# STX165R_UAVCAN_module.net
KiCad netlist of a schematic drawn in Altium Designer
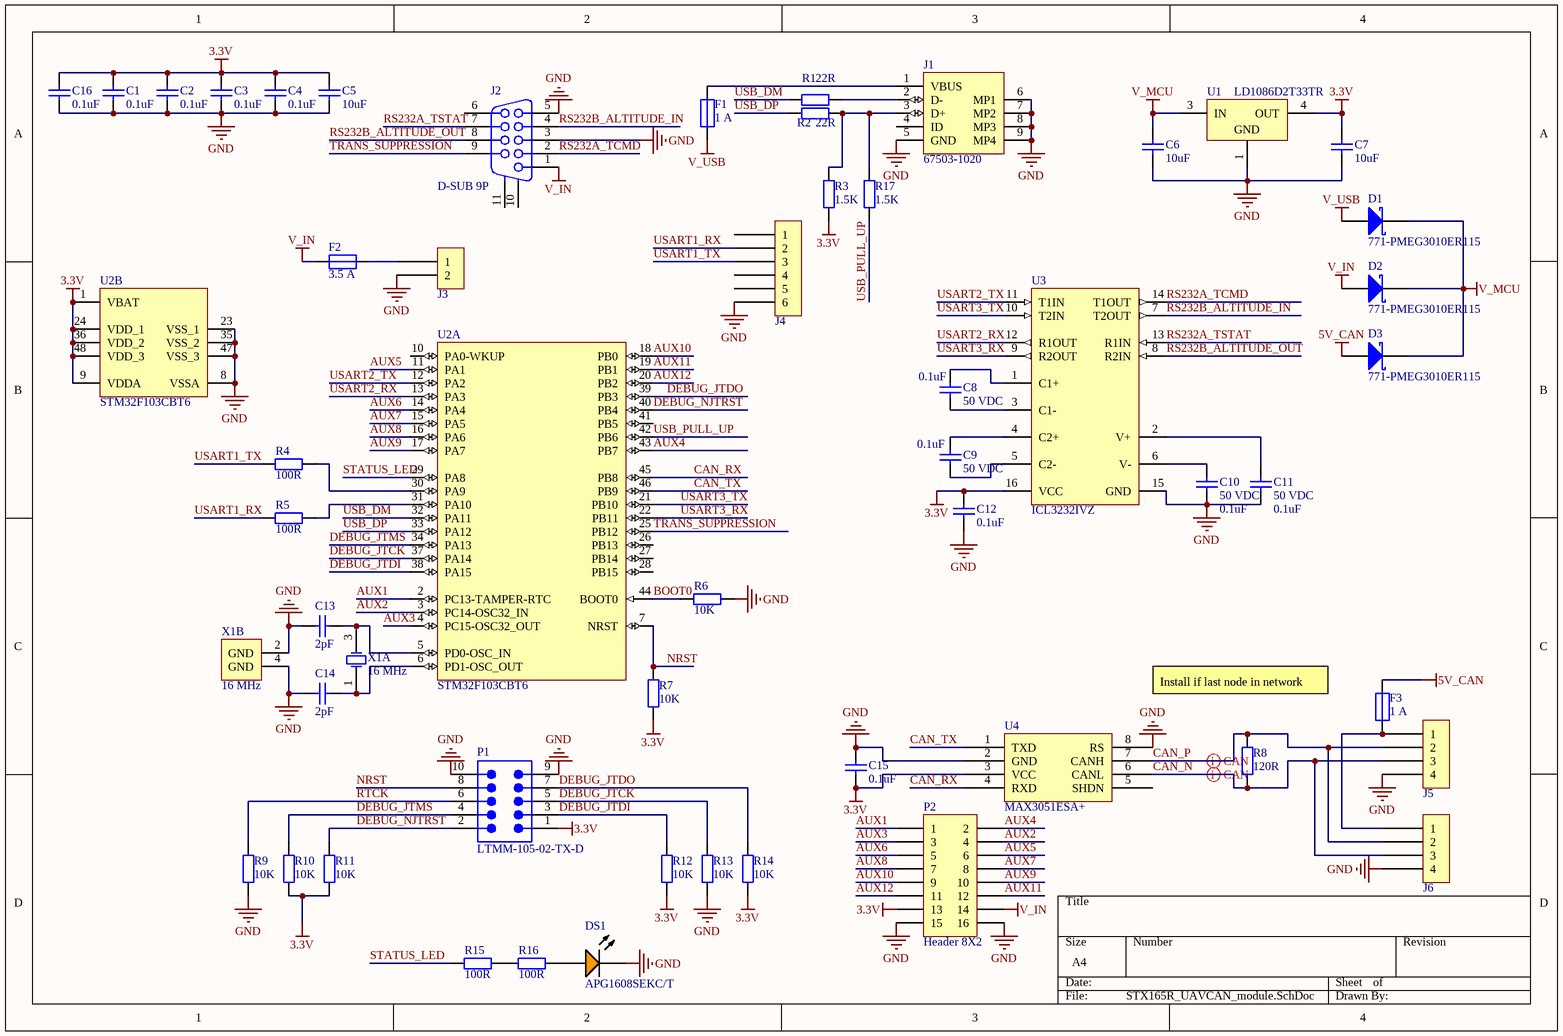
[diagram p0: STX165R_UAVCAN_module.SchDoc]

(export (version "E")
  (design (tool "Eeschema 10.0.6"))
  (components
    (comp (ref "C1")
      (value "0.1uF")
      (footprint "0603C_L")
      (description "CAP CER 0603 0.1uF 16V X7R 5%")
      (fields
        (field (name "MANUFACTURER") "Vishay / Vitramon")
        (field (name "MANUFACTURER PART NUMBER") "VJ0603Y104JXJPW1BC")
      )
      (libsource (lib "Capacitors") (part "VJ0603Y104JXJPW1BC"))
    )
    (comp (ref "C2")
      (value "0.1uF")
      (footprint "0603C_L")
      (description "CAP CER 0603 0.1uF 16V X7R 5%")
      (fields
        (field (name "MANUFACTURER") "Vishay / Vitramon")
        (field (name "MANUFACTURER PART NUMBER") "VJ0603Y104JXJPW1BC")
      )
      (libsource (lib "Capacitors") (part "VJ0603Y104JXJPW1BC"))
    )
    (comp (ref "C3")
      (value "0.1uF")
      (footprint "0603C_L")
      (description "CAP CER 0603 0.1uF 16V X7R 5%")
      (fields
        (field (name "MANUFACTURER") "Vishay / Vitramon")
        (field (name "MANUFACTURER PART NUMBER") "VJ0603Y104JXJPW1BC")
      )
      (libsource (lib "Capacitors") (part "VJ0603Y104JXJPW1BC"))
    )
    (comp (ref "C4")
      (value "0.1uF")
      (footprint "0603C_L")
      (description "CAP CER 0603 0.1uF 16V X7R 5%")
      (fields
        (field (name "MANUFACTURER") "Vishay / Vitramon")
        (field (name "MANUFACTURER PART NUMBER") "VJ0603Y104JXJPW1BC")
      )
      (libsource (lib "Capacitors") (part "VJ0603Y104JXJPW1BC"))
    )
    (comp (ref "C5")
      (value "10uF")
      (footprint "1206_1.6_L")
      (description "CAP CER 1206 10uF 25V X7R 10%")
      (fields
        (field (name "MANUFACTURER") "Taiyo Yuden")
        (field (name "MANUFACTURER PART NUMBER") "TMK316B7106KL-TD")
      )
      (libsource (lib "KMTI-main") (part "TMK316B7106KL-TD"))
    )
    (comp (ref "C6")
      (value "10uF")
      (footprint "1206_1.6_L")
      (description "CAP CER 1206 10uF 50V X5R 20%")
      (fields
        (field (name "MANUFACTURER") "Murata Electronics")
        (field (name "MANUFACTURER PART NUMBER") "GRM31CR61H106MA12L")
      )
      (libsource (lib "KMTI-main") (part "GRM31CR61H106MA12L"))
    )
    (comp (ref "C7")
      (value "10uF")
      (footprint "1206_1.6_L")
      (description "CAP CER 1206 10uF 25V X7R 10%")
      (fields
        (field (name "MANUFACTURER") "Taiyo Yuden")
        (field (name "MANUFACTURER PART NUMBER") "TMK316B7106KL-TD")
      )
      (libsource (lib "KMTI-main") (part "TMK316B7106KL-TD"))
    )
    (comp (ref "C8")
      (value "0.1uF")
      (footprint "0603C_L")
      (description "CAP CER 0603 0.1uF 50V X7R 10%")
      (fields
        (field (name "MANUFACTURER") "Murata Electronics")
        (field (name "MANUFACTURER PART NUMBER") "GRM188R71H104KA93D")
        (field (name "VOLTAGE RATING DC") "50 VDC")
      )
      (libsource (lib "KMTI-main") (part "GRM188R71H104KA93D"))
    )
    (comp (ref "C9")
      (value "0.1uF")
      (footprint "0603C_L")
      (description "CAP CER 0603 0.1uF 50V X7R 10%")
      (fields
        (field (name "MANUFACTURER") "Murata Electronics")
        (field (name "MANUFACTURER PART NUMBER") "GRM188R71H104KA93D")
        (field (name "VOLTAGE RATING DC") "50 VDC")
      )
      (libsource (lib "KMTI-main") (part "GRM188R71H104KA93D"))
    )
    (comp (ref "C10")
      (value "0.1uF")
      (footprint "0603C_L")
      (description "CAP CER 0603 0.1uF 50V X7R 10%")
      (fields
        (field (name "MANUFACTURER") "Murata Electronics")
        (field (name "MANUFACTURER PART NUMBER") "GRM188R71H104KA93D")
        (field (name "VOLTAGE RATING DC") "50 VDC")
      )
      (libsource (lib "KMTI-main") (part "GRM188R71H104KA93D"))
    )
    (comp (ref "C11")
      (value "0.1uF")
      (footprint "0603C_L")
      (description "CAP CER 0603 0.1uF 50V X7R 10%")
      (fields
        (field (name "MANUFACTURER") "Murata Electronics")
        (field (name "MANUFACTURER PART NUMBER") "GRM188R71H104KA93D")
        (field (name "VOLTAGE RATING DC") "50 VDC")
      )
      (libsource (lib "KMTI-main") (part "GRM188R71H104KA93D"))
    )
    (comp (ref "C12")
      (value "0.1uF")
      (footprint "0603C_L")
      (description "CAP CER 0603 0.1uF 16V X7R 5%")
      (fields
        (field (name "MANUFACTURER") "Vishay / Vitramon")
        (field (name "MANUFACTURER PART NUMBER") "VJ0603Y104JXJPW1BC")
      )
      (libsource (lib "KMTI-main") (part "VJ0603Y104JXJPW1BC"))
    )
    (comp (ref "C13")
      (value "2pF")
      (footprint "0603C_L")
      (description "CAP CER 2pF 0603 50V C0G 12.5%")
      (fields
        (field (name "MANUFACTURER") "TDK")
        (field (name "MANUFACTURER PART NUMBER") "C1608C0G1H020C080AA")
      )
      (libsource (lib "KMTI-main") (part "C1608C0G1H020C080AA"))
    )
    (comp (ref "C14")
      (value "2pF")
      (footprint "0603C_L")
      (description "CAP CER 2pF 0603 50V C0G 12.5%")
      (fields
        (field (name "MANUFACTURER") "TDK")
        (field (name "MANUFACTURER PART NUMBER") "C1608C0G1H020C080AA")
      )
      (libsource (lib "KMTI-main") (part "C1608C0G1H020C080AA"))
    )
    (comp (ref "C15")
      (value "0.1uF")
      (footprint "0603C_L")
      (description "CAP CER 0603 0.1uF 16V X7R 5%")
      (fields
        (field (name "MANUFACTURER") "Vishay / Vitramon")
        (field (name "MANUFACTURER PART NUMBER") "VJ0603Y104JXJPW1BC")
      )
      (libsource (lib "KMTI-main") (part "VJ0603Y104JXJPW1BC"))
    )
    (comp (ref "C16")
      (value "0.1uF")
      (footprint "0603C_L")
      (description "CAP CER 0603 0.1uF 16V X7R 5%")
      (fields
        (field (name "MANUFACTURER") "Vishay / Vitramon")
        (field (name "MANUFACTURER PART NUMBER") "VJ0603Y104JXJPW1BC")
      )
      (libsource (lib "Capacitors") (part "VJ0603Y104JXJPW1BC"))
    )
    (comp (ref "D1")
      (value "PMEG3010ER,115")
      (footprint "SOD123W_L")
      (description "Schottky Diodes & Rectifiers SCHOTTKY DIODE")
      (fields
        (field (name "MANUFACTURER") "NXP Semiconductors")
        (field (name "SUPPLIER PART NUMBER 1") "771-PMEG3010ER115")
      )
      (libsource (lib "KMTI-main") (part "PMEG3010ER,115"))
    )
    (comp (ref "D2")
      (value "PMEG3010ER,115")
      (footprint "SOD123W_L")
      (description "Schottky Diodes & Rectifiers SCHOTTKY DIODE")
      (fields
        (field (name "MANUFACTURER") "NXP Semiconductors")
        (field (name "SUPPLIER PART NUMBER 1") "771-PMEG3010ER115")
      )
      (libsource (lib "KMTI-main") (part "PMEG3010ER,115"))
    )
    (comp (ref "D3")
      (value "PMEG3010ER,115")
      (footprint "SOD123W_L")
      (description "Schottky Diodes & Rectifiers SCHOTTKY DIODE")
      (fields
        (field (name "MANUFACTURER") "NXP Semiconductors")
        (field (name "SUPPLIER PART NUMBER 1") "771-PMEG3010ER115")
      )
      (libsource (lib "KMTI-main") (part "PMEG3010ER,115"))
    )
    (comp (ref "DS1")
      (value "APG1608SEKC/T")
      (footprint "KING-LED0603-25-ORANGE_V")
      (description "LED, SMT, 0603(1608), 0.25mm Tthickness, Super Bright Orange")
      (libsource (lib "Altium Content Vault") (part "KING-LED_ORANGE_A1K2-2"))
    )
    (comp (ref "F1")
      (value "F0603E1R00FSTR")
      (footprint "0603R_0.45_L")
      (description "FUSE 0603 1.0A FAST")
      (fields (field (name "MANUFACTURER") "AVX") (field (name "CURRENT RATING") "1 A"))
      (libsource (lib "KMTI-main") (part "F0603E1R00FSTR"))
    )
    (comp (ref "F2")
      (value "0603SFV350F/32-2")
      (footprint "0603R_0.45_L")
      (description "FUSE 0603 3.5A FAST")
      (fields
        (field (name "MANUFACTURER") "TE Connectivity / Raychem")
        (field (name "CURRENT RATING") "3.5 A")
      )
      (libsource (lib "KMTI-main") (part "0603SFV350F/32-2"))
    )
    (comp (ref "F3")
      (value "F0603E1R00FSTR")
      (footprint "0603R_0.45_L")
      (description "FUSE 0603 1.0A FAST")
      (fields (field (name "MANUFACTURER") "AVX") (field (name "CURRENT RATING") "1 A"))
      (libsource (lib "KMTI-main") (part "F0603E1R00FSTR"))
    )
    (comp (ref "J1")
      (value "67503-1020")
      (footprint "MOLX-67503-1020_V")
      (description "USB, MINI, SMD, RA KME04-USBMU03A01")
      (fields (field (name "MANUFACTURER") "Molex"))
      (libsource (lib "Altium Content Vault") (part "MOLX-67503-1020"))
    )
    (comp (ref "J2")
      (value "D-SUB 9P")
      (footprint "1-1634222-2")
      (description "Receptacle Header Assemby")
      (libsource (lib "Misc_connectors") (part "D-SUB-9P"))
    )
    (comp (ref "J3")
      (value "43650-0224")
      (footprint "43650-0224")
      (description "Headers & Wire Housings MICRO-FIT 3.0 HEADER")
      (fields (field (name "MANUFACTURER") "Molex"))
      (libsource (lib "KMTI-main") (part "43650-0224"))
    )
    (comp (ref "J4")
      (value "BM06B-GHS-TBT(LF)(SN)(N)")
      (footprint "BM06B-GHS-TBT")
      (description "CONN HEADER GH TOP 6POS 1.25MM")
      (fields (field (name "MANUFACTURER") "JST Sales America Inc."))
      (libsource (lib "JST") (part "BM06B-GHS-TBT(LF)(SN)(N)"))
    )
    (comp (ref "J5")
      (value "BM04B-GHS-TBT(LF)(SN)(N)")
      (footprint "BM04B-GHS-TBT")
      (description "CONN HEADER GH TOP 4POS 1.25MM")
      (fields (field (name "MANUFACTURER") "JST Sales America Inc."))
      (libsource (lib "JST") (part "BM04B-GHS-TBT(LF)(SN)(N)"))
    )
    (comp (ref "J6")
      (value "BM04B-GHS-TBT(LF)(SN)(N)")
      (footprint "BM04B-GHS-TBT")
      (description "CONN HEADER GH TOP 4POS 1.25MM")
      (fields (field (name "MANUFACTURER") "JST Sales America Inc."))
      (libsource (lib "JST") (part "BM04B-GHS-TBT(LF)(SN)(N)"))
    )
    (comp (ref "P1")
      (value "LTMM-105-02-TX-D")
      (footprint "SMTC-LTMM-105-02-XX-D")
      (description "Shrouded Header & Stacker, Through-Hole, Vertical, -55 to 105 degC, 2 mm Pitch, 10-Pin, Male, RoHS")
      (fields (field (name "MANUFACTURER") "Samtec"))
      (libsource (lib "Altium Content Vault") (part "CMP-1028-00010-1"))
    )
    (comp (ref "P2")
      (value "Header 8X2")
      (footprint "HDR2X8")
      (description "Header, 8-Pin, Dual row")
      (fields (field (name "PUBLISHER") "Altium Limited"))
      (libsource (lib "Miscellaneous Connectors") (part "Header 8X2"))
    )
    (comp (ref "R1")
      (value "22R")
      (footprint "0603R_0.45_L")
      (description "RES 0603 22R 5% 100mW")
      (fields
        (field (name "MANUFACTURER") "Vishay / Dale")
        (field (name "MANUFACTURER PART NUMBER") "CRCW060322R0JNEB")
      )
      (libsource (lib "KMTI-main") (part "CRCW060322R0JNEB"))
    )
    (comp (ref "R2")
      (value "22R")
      (footprint "0603R_0.45_L")
      (description "RES 0603 22R 5% 100mW")
      (fields
        (field (name "MANUFACTURER") "Vishay / Dale")
        (field (name "MANUFACTURER PART NUMBER") "CRCW060322R0JNEB")
      )
      (libsource (lib "KMTI-main") (part "CRCW060322R0JNEB"))
    )
    (comp (ref "R3")
      (value "1.5K")
      (footprint "0603R_0.45_L")
      (description "RES 0603 1.5K 5% 100mW")
      (fields
        (field (name "MANUFACTURER") "Vishay / Dale")
        (field (name "MANUFACTURER PART NUMBER") "CRCW06031K50JNEB")
      )
      (libsource (lib "KMTI-main") (part "CRCW06031K50JNEB"))
    )
    (comp (ref "R4")
      (value "100R")
      (footprint "0603R_0.45_L")
      (description "RES 0603 100R 5% 100mW")
      (fields
        (field (name "MANUFACTURER") "Vishay / Dale")
        (field (name "MANUFACTURER PART NUMBER") "CRCW0603100RJNEB")
      )
      (libsource (lib "KMTI-main") (part "CRCW0603100RJNEB"))
    )
    (comp (ref "R5")
      (value "100R")
      (footprint "0603R_0.45_L")
      (description "RES 0603 100R 5% 100mW")
      (fields
        (field (name "MANUFACTURER") "Vishay / Dale")
        (field (name "MANUFACTURER PART NUMBER") "CRCW0603100RJNEB")
      )
      (libsource (lib "KMTI-main") (part "CRCW0603100RJNEB"))
    )
    (comp (ref "R6")
      (value "10K")
      (footprint "0603R_0.45_L")
      (description "RES 0603 10K 5% 100mW")
      (fields
        (field (name "MANUFACTURER") "Vishay / Dale")
        (field (name "MANUFACTURER PART NUMBER") "CRCW060310K0JNEB")
      )
      (libsource (lib "") (part "CRCW060310K0JNEB_1"))
    )
    (comp (ref "R7")
      (value "10K")
      (footprint "0603R_0.45_L")
      (description "RES 0603 10K 5% 100mW")
      (fields
        (field (name "MANUFACTURER") "Vishay / Dale")
        (field (name "MANUFACTURER PART NUMBER") "CRCW060310K0JNEB")
      )
      (libsource (lib "KMTI-main") (part "CRCW060310K0JNEB"))
    )
    (comp (ref "R8")
      (value "120R")
      (footprint "0603R_0.45_L")
      (description "RES 0603 120R 5% 100mW")
      (fields
        (field (name "MANUFACTURER") "Vishay / Dale")
        (field (name "MANUFACTURER PART NUMBER") "CRCW0603120RJNEB")
      )
      (libsource (lib "KMTI-main") (part "CRCW0603120RJNEB"))
    )
    (comp (ref "R9")
      (value "10K")
      (footprint "0603R_0.45_L")
      (description "RES 0603 10K 5% 100mW")
      (fields
        (field (name "MANUFACTURER") "Vishay / Dale")
        (field (name "MANUFACTURER PART NUMBER") "CRCW060310K0JNEB")
      )
      (libsource (lib "KMTI-main") (part "CRCW060310K0JNEB"))
    )
    (comp (ref "R10")
      (value "10K")
      (footprint "0603R_0.45_L")
      (description "RES 0603 10K 5% 100mW")
      (fields
        (field (name "MANUFACTURER") "Vishay / Dale")
        (field (name "MANUFACTURER PART NUMBER") "CRCW060310K0JNEB")
      )
      (libsource (lib "KMTI-main") (part "CRCW060310K0JNEB"))
    )
    (comp (ref "R11")
      (value "10K")
      (footprint "0603R_0.45_L")
      (description "RES 0603 10K 5% 100mW")
      (fields
        (field (name "MANUFACTURER") "Vishay / Dale")
        (field (name "MANUFACTURER PART NUMBER") "CRCW060310K0JNEB")
      )
      (libsource (lib "KMTI-main") (part "CRCW060310K0JNEB"))
    )
    (comp (ref "R12")
      (value "10K")
      (footprint "0603R_0.45_L")
      (description "RES 0603 10K 5% 100mW")
      (fields
        (field (name "MANUFACTURER") "Vishay / Dale")
        (field (name "MANUFACTURER PART NUMBER") "CRCW060310K0JNEB")
      )
      (libsource (lib "KMTI-main") (part "CRCW060310K0JNEB"))
    )
    (comp (ref "R13")
      (value "10K")
      (footprint "0603R_0.45_L")
      (description "RES 0603 10K 5% 100mW")
      (fields
        (field (name "MANUFACTURER") "Vishay / Dale")
        (field (name "MANUFACTURER PART NUMBER") "CRCW060310K0JNEB")
      )
      (libsource (lib "KMTI-main") (part "CRCW060310K0JNEB"))
    )
    (comp (ref "R14")
      (value "10K")
      (footprint "0603R_0.45_L")
      (description "RES 0603 10K 5% 100mW")
      (fields
        (field (name "MANUFACTURER") "Vishay / Dale")
        (field (name "MANUFACTURER PART NUMBER") "CRCW060310K0JNEB")
      )
      (libsource (lib "KMTI-main") (part "CRCW060310K0JNEB"))
    )
    (comp (ref "R15")
      (value "100R")
      (footprint "0603R_0.45_L")
      (description "RES 0603 100R 5% 100mW")
      (fields
        (field (name "MANUFACTURER") "Vishay / Dale")
        (field (name "MANUFACTURER PART NUMBER") "CRCW0603100RJNEB")
      )
      (libsource (lib "") (part "CRCW0603100RJNEB_1"))
    )
    (comp (ref "R16")
      (value "100R")
      (footprint "0603R_0.45_L")
      (description "RES 0603 100R 5% 100mW")
      (fields
        (field (name "MANUFACTURER") "Vishay / Dale")
        (field (name "MANUFACTURER PART NUMBER") "CRCW0603100RJNEB")
      )
      (libsource (lib "KMTI-main") (part "CRCW0603100RJNEB"))
    )
    (comp (ref "R17")
      (value "1.5K")
      (footprint "0603R_0.45_L")
      (description "RES 0603 1.5K 5% 100mW")
      (fields
        (field (name "MANUFACTURER") "Vishay / Dale")
        (field (name "MANUFACTURER PART NUMBER") "CRCW06031K50JNEB")
      )
      (libsource (lib "KMTI-main") (part "CRCW06031K50JNEB"))
    )
    (comp (ref "U1")
      (value "LD1086D2T33TR")
      (footprint "TO-263_N")
      (description "1.5A, Low Drop Positive Voltage Regulator, 3.3V, 3-Pin D2PAK, Tape and Reel")
      (libsource (lib "Altium Content Vault") (part "CMP-0244-00124-1"))
    )
    (comp (ref "U2")
      (value "STM32F103CBT6")
      (footprint "STM-LQFP48_L")
      (libsource (lib "Altium Content Vault") (part "MC-ARM-STM32F103X8_B-SQ48"))
    )
    (comp (ref "U3")
      (value "ICL3232IVZ")
      (footprint "TSSOP16_L")
      (description "RS-232 Interface IC RS232 3V 2D/2R IND")
      (fields (field (name "MANUFACTURER") "Intersil"))
      (libsource (lib "KMTI-main") (part "ICL3232IVZ"))
    )
    (comp (ref "U4")
      (value "MAX3051ESA+")
      (footprint "SOIC8_L")
      (description "CAN Interface IC 3.3V 1Mbps Transceiver")
      (fields (field (name "MANUFACTURER") "Maxim Integrated"))
      (libsource (lib "KMTI-main") (part "MAX3051ESA+"))
    )
    (comp (ref "X1")
      (value "CRYS 16MHz 9pF")
      (footprint "TSX-3225 16.0000MF09Z-AC3")
      (description "Crystals 16MHz 10ppm 9pF -20C +75C")
      (fields
        (field (name "MANUFACTURER") "Epson Timing")
        (field (name "MANUFACTURER PART NUMBER") "TSX-3225 16.0000MF09Z-AC3")
        (field (name "FREQUENCY") "16 MHz")
      )
      (libsource (lib "KMTI-main") (part "TSX-3225 16.0000MF09Z-AC3"))
    )
  )
  (nets
    (net (code "1") (name "/AUX1") (class "Default")
      (node (ref "P2") (pin "1") (pinfunction "1_1") (pintype "passive"))
      (node (ref "U2") (pin "2") (pinfunction "PC13-TAMPER-RTC_2") (pintype "bidirectional"))
    )
    (net (code "2") (name "/AUX2") (class "Default")
      (node (ref "P2") (pin "4") (pinfunction "4_4") (pintype "passive"))
      (node (ref "U2") (pin "3") (pinfunction "PC14-OSC32_IN_3") (pintype "bidirectional"))
    )
    (net (code "3") (name "/AUX3") (class "Default")
      (node (ref "P2") (pin "3") (pinfunction "3_3") (pintype "passive"))
      (node (ref "U2") (pin "4") (pinfunction "PC15-OSC32_OUT_4") (pintype "bidirectional"))
    )
    (net (code "4") (name "/AUX4") (class "Default")
      (node (ref "P2") (pin "2") (pinfunction "2_2") (pintype "passive"))
      (node (ref "U2") (pin "43") (pinfunction "PB7_43") (pintype "bidirectional"))
    )
    (net (code "5") (name "/AUX5") (class "Default")
      (node (ref "P2") (pin "6") (pinfunction "6_6") (pintype "passive"))
      (node (ref "U2") (pin "11") (pinfunction "PA1_11") (pintype "bidirectional"))
    )
    (net (code "6") (name "/AUX6") (class "Default")
      (node (ref "P2") (pin "5") (pinfunction "5_5") (pintype "passive"))
      (node (ref "U2") (pin "14") (pinfunction "PA4_14") (pintype "bidirectional"))
    )
    (net (code "7") (name "/AUX7") (class "Default")
      (node (ref "P2") (pin "8") (pinfunction "8_8") (pintype "passive"))
      (node (ref "U2") (pin "15") (pinfunction "PA5_15") (pintype "bidirectional"))
    )
    (net (code "8") (name "/AUX8") (class "Default")
      (node (ref "P2") (pin "7") (pinfunction "7_7") (pintype "passive"))
      (node (ref "U2") (pin "16") (pinfunction "PA6_16") (pintype "bidirectional"))
    )
    (net (code "9") (name "/AUX9") (class "Default")
      (node (ref "P2") (pin "10") (pinfunction "10_10") (pintype "passive"))
      (node (ref "U2") (pin "17") (pinfunction "PA7_17") (pintype "bidirectional"))
    )
    (net (code "10") (name "/AUX10") (class "Default")
      (node (ref "P2") (pin "9") (pinfunction "9_9") (pintype "passive"))
      (node (ref "U2") (pin "18") (pinfunction "PB0_18") (pintype "bidirectional"))
    )
    (net (code "11") (name "/AUX11") (class "Default")
      (node (ref "P2") (pin "12") (pinfunction "12_12") (pintype "passive"))
      (node (ref "U2") (pin "19") (pinfunction "PB1_19") (pintype "bidirectional"))
    )
    (net (code "12") (name "/AUX12") (class "Default")
      (node (ref "P2") (pin "11") (pinfunction "11_11") (pintype "passive"))
      (node (ref "U2") (pin "20") (pinfunction "PB2_20") (pintype "bidirectional"))
    )
    (net (code "13") (name "/BOOT0") (class "Default")
      (node (ref "R6") (pin "2") (pinfunction "2_2") (pintype "passive"))
      (node (ref "U2") (pin "44") (pinfunction "BOOT0_44") (pintype "input"))
    )
    (net (code "14") (name "/CAN_N") (class "Default")
      (node (ref "J5") (pin "3") (pinfunction "3_3") (pintype "passive"))
      (node (ref "J6") (pin "3") (pinfunction "3_3") (pintype "passive"))
      (node (ref "R8") (pin "1") (pinfunction "1_1") (pintype "passive"))
      (node (ref "U4") (pin "6") (pinfunction "CANL_6") (pintype "passive"))
    )
    (net (code "15") (name "/CAN_P") (class "Default")
      (node (ref "J5") (pin "2") (pinfunction "2_2") (pintype "passive"))
      (node (ref "J6") (pin "2") (pinfunction "2_2") (pintype "passive"))
      (node (ref "R8") (pin "2") (pinfunction "2_2") (pintype "passive"))
      (node (ref "U4") (pin "7") (pinfunction "CANH_7") (pintype "passive"))
    )
    (net (code "16") (name "/CAN_RX") (class "Default")
      (node (ref "U2") (pin "45") (pinfunction "PB8_45") (pintype "bidirectional"))
      (node (ref "U4") (pin "4") (pinfunction "RXD_4") (pintype "passive"))
    )
    (net (code "17") (name "/CAN_TX") (class "Default")
      (node (ref "U2") (pin "46") (pinfunction "PB9_46") (pintype "bidirectional"))
      (node (ref "U4") (pin "1") (pinfunction "TXD_1") (pintype "passive"))
    )
    (net (code "18") (name "/DEBUG_JTCK") (class "Default")
      (node (ref "P1") (pin "5") (pinfunction "5_5") (pintype "passive"))
      (node (ref "R13") (pin "2") (pinfunction "2_2") (pintype "passive"))
      (node (ref "U2") (pin "37") (pinfunction "PA14_37") (pintype "bidirectional"))
    )
    (net (code "19") (name "/DEBUG_JTDI") (class "Default")
      (node (ref "P1") (pin "3") (pinfunction "3_3") (pintype "passive"))
      (node (ref "R12") (pin "2") (pinfunction "2_2") (pintype "passive"))
      (node (ref "U2") (pin "38") (pinfunction "PA15_38") (pintype "bidirectional"))
    )
    (net (code "20") (name "/DEBUG_JTDO") (class "Default")
      (node (ref "P1") (pin "7") (pinfunction "7_7") (pintype "passive"))
      (node (ref "R14") (pin "2") (pinfunction "2_2") (pintype "passive"))
      (node (ref "U2") (pin "39") (pinfunction "PB3_39") (pintype "bidirectional"))
    )
    (net (code "21") (name "/DEBUG_JTMS") (class "Default")
      (node (ref "P1") (pin "4") (pinfunction "4_4") (pintype "passive"))
      (node (ref "R10") (pin "2") (pinfunction "2_2") (pintype "passive"))
      (node (ref "U2") (pin "34") (pinfunction "PA13_34") (pintype "bidirectional"))
    )
    (net (code "22") (name "/DEBUG_NJTRST") (class "Default")
      (node (ref "P1") (pin "2") (pinfunction "2_2") (pintype "passive"))
      (node (ref "R11") (pin "2") (pinfunction "2_2") (pintype "passive"))
      (node (ref "U2") (pin "40") (pinfunction "PB4_40") (pintype "bidirectional"))
    )
    (net (code "23") (name "/NRST") (class "Default")
      (node (ref "P1") (pin "8") (pinfunction "8_8") (pintype "passive"))
      (node (ref "R7") (pin "2") (pinfunction "2_2") (pintype "passive"))
      (node (ref "U2") (pin "7") (pinfunction "NRST_7") (pintype "bidirectional"))
    )
    (net (code "24") (name "/RS232A_TCMD") (class "Default")
      (node (ref "J2") (pin "2") (pinfunction "2_2") (pintype "passive"))
      (node (ref "U3") (pin "14") (pinfunction "T1OUT_14") (pintype "output"))
    )
    (net (code "25") (name "/RS232A_TSTAT") (class "Default")
      (node (ref "J2") (pin "7") (pinfunction "7_7") (pintype "passive"))
      (node (ref "U3") (pin "13") (pinfunction "R1IN_13") (pintype "input"))
    )
    (net (code "26") (name "/RS232B_ALTITUDE_IN") (class "Default")
      (node (ref "J2") (pin "4") (pinfunction "4_4") (pintype "passive"))
      (node (ref "U3") (pin "7") (pinfunction "T2OUT_7") (pintype "output"))
    )
    (net (code "27") (name "/RS232B_ALTITUDE_OUT") (class "Default")
      (node (ref "J2") (pin "8") (pinfunction "8_8") (pintype "passive"))
      (node (ref "U3") (pin "8") (pinfunction "R2IN_8") (pintype "input"))
    )
    (net (code "28") (name "/RTCK") (class "Default")
      (node (ref "P1") (pin "6") (pinfunction "6_6") (pintype "passive"))
      (node (ref "R9") (pin "2") (pinfunction "2_2") (pintype "passive"))
    )
    (net (code "29") (name "/STATUS_LED") (class "Default")
      (node (ref "R15") (pin "2") (pinfunction "2_2") (pintype "passive"))
      (node (ref "U2") (pin "29") (pinfunction "PA8_29") (pintype "bidirectional"))
    )
    (net (code "30") (name "/TRANS_SUPPRESSION") (class "Default")
      (node (ref "J2") (pin "9") (pinfunction "9_9") (pintype "passive"))
      (node (ref "U2") (pin "25") (pinfunction "PB12_25") (pintype "bidirectional"))
    )
    (net (code "31") (name "/USART1_RX") (class "Default")
      (node (ref "J4") (pin "2") (pinfunction "2_2") (pintype "passive"))
      (node (ref "R5") (pin "1") (pinfunction "1_1") (pintype "passive"))
    )
    (net (code "32") (name "/USART1_TX") (class "Default")
      (node (ref "J4") (pin "3") (pinfunction "3_3") (pintype "passive"))
      (node (ref "R4") (pin "1") (pinfunction "1_1") (pintype "passive"))
    )
    (net (code "33") (name "/USART2_RX") (class "Default")
      (node (ref "U2") (pin "13") (pinfunction "PA3_13") (pintype "bidirectional"))
      (node (ref "U3") (pin "12") (pinfunction "R1OUT_12") (pintype "output"))
    )
    (net (code "34") (name "/USART2_TX") (class "Default")
      (node (ref "U2") (pin "12") (pinfunction "PA2_12") (pintype "bidirectional"))
      (node (ref "U3") (pin "11") (pinfunction "T1IN_11") (pintype "input"))
    )
    (net (code "35") (name "/USART3_RX") (class "Default")
      (node (ref "U2") (pin "22") (pinfunction "PB11_22") (pintype "bidirectional"))
      (node (ref "U3") (pin "9") (pinfunction "R2OUT_9") (pintype "output"))
    )
    (net (code "36") (name "/USART3_TX") (class "Default")
      (node (ref "U2") (pin "21") (pinfunction "PB10_21") (pintype "bidirectional"))
      (node (ref "U3") (pin "10") (pinfunction "T2IN_10") (pintype "input"))
    )
    (net (code "37") (name "/USB_DM") (class "Default")
      (node (ref "R1") (pin "1") (pinfunction "1_1") (pintype "passive"))
      (node (ref "U2") (pin "32") (pinfunction "PA11_32") (pintype "bidirectional"))
    )
    (net (code "38") (name "/USB_DP") (class "Default")
      (node (ref "R2") (pin "1") (pinfunction "1_1") (pintype "passive"))
      (node (ref "U2") (pin "33") (pinfunction "PA12_33") (pintype "bidirectional"))
    )
    (net (code "39") (name "/USB_PULL_UP") (class "Default")
      (node (ref "R17") (pin "1") (pinfunction "1_1") (pintype "passive"))
      (node (ref "U2") (pin "42") (pinfunction "PB6_42") (pintype "bidirectional"))
    )
    (net (code "40") (name "3.3V") (class "Default")
      (node (ref "C1") (pin "2") (pinfunction "2_2") (pintype "passive"))
      (node (ref "C12") (pin "2") (pinfunction "2_2") (pintype "passive"))
      (node (ref "C15") (pin "1") (pinfunction "1_1") (pintype "passive"))
      (node (ref "C16") (pin "2") (pinfunction "2_2") (pintype "passive"))
      (node (ref "C2") (pin "2") (pinfunction "2_2") (pintype "passive"))
      (node (ref "C3") (pin "2") (pinfunction "2_2") (pintype "passive"))
      (node (ref "C4") (pin "2") (pinfunction "2_2") (pintype "passive"))
      (node (ref "C5") (pin "2") (pinfunction "2_2") (pintype "passive"))
      (node (ref "C7") (pin "2") (pinfunction "2_2") (pintype "passive"))
      (node (ref "P1") (pin "1") (pinfunction "1_1") (pintype "passive"))
      (node (ref "P2") (pin "13") (pinfunction "13_13") (pintype "passive"))
      (node (ref "R10") (pin "1") (pinfunction "1_1") (pintype "passive"))
      (node (ref "R11") (pin "1") (pinfunction "1_1") (pintype "passive"))
      (node (ref "R12") (pin "1") (pinfunction "1_1") (pintype "passive"))
      (node (ref "R14") (pin "1") (pinfunction "1_1") (pintype "passive"))
      (node (ref "R3") (pin "1") (pinfunction "1_1") (pintype "passive"))
      (node (ref "R7") (pin "1") (pinfunction "1_1") (pintype "passive"))
      (node (ref "U1") (pin "4") (pinfunction "OUT_4") (pintype "power_in"))
      (node (ref "U2") (pin "1") (pinfunction "VBAT_1") (pintype "power_in"))
      (node (ref "U2") (pin "24") (pinfunction "VDD_1_24") (pintype "power_in"))
      (node (ref "U2") (pin "36") (pinfunction "VDD_2_36") (pintype "power_in"))
      (node (ref "U2") (pin "48") (pinfunction "VDD_3_48") (pintype "power_in"))
      (node (ref "U2") (pin "9") (pinfunction "VDDA_9") (pintype "power_in"))
      (node (ref "U3") (pin "16") (pinfunction "VCC_16") (pintype "power_in"))
      (node (ref "U4") (pin "3") (pinfunction "VCC_3") (pintype "passive"))
    )
    (net (code "41") (name "5V_CAN") (class "Default")
      (node (ref "D3") (pin "2") (pinfunction "A_2") (pintype "passive"))
      (node (ref "F3") (pin "2") (pinfunction "2_2") (pintype "passive"))
    )
    (net (code "42") (name "GND") (class "Default")
      (node (ref "C1") (pin "1") (pinfunction "1_1") (pintype "passive"))
      (node (ref "C10") (pin "1") (pinfunction "1_1") (pintype "passive"))
      (node (ref "C11") (pin "1") (pinfunction "1_1") (pintype "passive"))
      (node (ref "C12") (pin "1") (pinfunction "1_1") (pintype "passive"))
      (node (ref "C13") (pin "1") (pinfunction "1_1") (pintype "passive"))
      (node (ref "C14") (pin "1") (pinfunction "1_1") (pintype "passive"))
      (node (ref "C15") (pin "2") (pinfunction "2_2") (pintype "passive"))
      (node (ref "C16") (pin "1") (pinfunction "1_1") (pintype "passive"))
      (node (ref "C2") (pin "1") (pinfunction "1_1") (pintype "passive"))
      (node (ref "C3") (pin "1") (pinfunction "1_1") (pintype "passive"))
      (node (ref "C4") (pin "1") (pinfunction "1_1") (pintype "passive"))
      (node (ref "C5") (pin "1") (pinfunction "1_1") (pintype "passive"))
      (node (ref "C6") (pin "1") (pinfunction "1_1") (pintype "passive"))
      (node (ref "C7") (pin "1") (pinfunction "1_1") (pintype "passive"))
      (node (ref "DS1") (pin "2") (pinfunction "K_2") (pintype "passive"))
      (node (ref "J1") (pin "5") (pinfunction "GND_5") (pintype "power_in"))
      (node (ref "J1") (pin "6") (pinfunction "MP1_6") (pintype "passive"))
      (node (ref "J1") (pin "7") (pinfunction "MP2_7") (pintype "passive"))
      (node (ref "J1") (pin "8") (pinfunction "MP3_8") (pintype "passive"))
      (node (ref "J1") (pin "9") (pinfunction "MP4_9") (pintype "passive"))
      (node (ref "J2") (pin "3") (pinfunction "3_3") (pintype "passive"))
      (node (ref "J2") (pin "5") (pinfunction "5_5") (pintype "passive"))
      (node (ref "J3") (pin "2") (pinfunction "2_2") (pintype "passive"))
      (node (ref "J4") (pin "6") (pinfunction "6_6") (pintype "passive"))
      (node (ref "J5") (pin "4") (pinfunction "4_4") (pintype "passive"))
      (node (ref "J6") (pin "4") (pinfunction "4_4") (pintype "passive"))
      (node (ref "P1") (pin "10") (pinfunction "10_10") (pintype "passive"))
      (node (ref "P1") (pin "9") (pinfunction "9_9") (pintype "passive"))
      (node (ref "P2") (pin "15") (pinfunction "15_15") (pintype "passive"))
      (node (ref "P2") (pin "16") (pinfunction "16_16") (pintype "passive"))
      (node (ref "R13") (pin "1") (pinfunction "1_1") (pintype "passive"))
      (node (ref "R6") (pin "1") (pinfunction "1_1") (pintype "passive"))
      (node (ref "R9") (pin "1") (pinfunction "1_1") (pintype "passive"))
      (node (ref "U1") (pin "1") (pinfunction "GND_1") (pintype "power_in"))
      (node (ref "U2") (pin "23") (pinfunction "VSS_1_23") (pintype "power_in"))
      (node (ref "U2") (pin "35") (pinfunction "VSS_2_35") (pintype "power_in"))
      (node (ref "U2") (pin "47") (pinfunction "VSS_3_47") (pintype "power_in"))
      (node (ref "U2") (pin "8") (pinfunction "VSSA_8") (pintype "power_in"))
      (node (ref "U3") (pin "15") (pinfunction "GND_15") (pintype "power_in"))
      (node (ref "U4") (pin "2") (pinfunction "GND_2") (pintype "passive"))
      (node (ref "U4") (pin "8") (pinfunction "RS_8") (pintype "passive"))
      (node (ref "X1") (pin "2") (pinfunction "GND_2") (pintype "power_in"))
      (node (ref "X1") (pin "4") (pinfunction "GND_4") (pintype "power_in"))
    )
    (net (code "43") (name "Net-(DS1-A)") (class "Default")
      (node (ref "DS1") (pin "1") (pinfunction "A_1") (pintype "passive"))
      (node (ref "R16") (pin "2") (pinfunction "2_2") (pintype "passive"))
    )
    (net (code "44") (name "Net-(F2-Pad2)") (class "Default")
      (node (ref "F2") (pin "2") (pinfunction "2_2") (pintype "passive"))
      (node (ref "J3") (pin "1") (pinfunction "1_1") (pintype "passive"))
    )
    (net (code "45") (name "Net-(F3-Pad1)") (class "Default")
      (node (ref "F3") (pin "1") (pinfunction "1_1") (pintype "passive"))
      (node (ref "J5") (pin "1") (pinfunction "1_1") (pintype "passive"))
      (node (ref "J6") (pin "1") (pinfunction "1_1") (pintype "passive"))
    )
    (net (code "46") (name "Net-(J1-D+)") (class "Default")
      (node (ref "J1") (pin "3") (pinfunction "D+_3") (pintype "bidirectional"))
      (node (ref "R17") (pin "2") (pinfunction "2_2") (pintype "passive"))
      (node (ref "R2") (pin "2") (pinfunction "2_2") (pintype "passive"))
      (node (ref "R3") (pin "2") (pinfunction "2_2") (pintype "passive"))
    )
    (net (code "47") (name "Net-(J1-D-)") (class "Default")
      (node (ref "J1") (pin "2") (pinfunction "D-_2") (pintype "bidirectional"))
      (node (ref "R1") (pin "2") (pinfunction "2_2") (pintype "passive"))
    )
    (net (code "48") (name "Net-(J1-VBUS)") (class "Default")
      (node (ref "F1") (pin "2") (pinfunction "2_2") (pintype "passive"))
      (node (ref "J1") (pin "1") (pinfunction "VBUS_1") (pintype "power_in"))
    )
    (net (code "49") (name "Net-(R15-Pad1)") (class "Default")
      (node (ref "R15") (pin "1") (pinfunction "1_1") (pintype "passive"))
      (node (ref "R16") (pin "1") (pinfunction "1_1") (pintype "passive"))
    )
    (net (code "50") (name "Net-(U2A-PA9)") (class "Default")
      (node (ref "R4") (pin "2") (pinfunction "2_2") (pintype "passive"))
      (node (ref "U2") (pin "30") (pinfunction "PA9_30") (pintype "bidirectional"))
    )
    (net (code "51") (name "Net-(U2A-PA10)") (class "Default")
      (node (ref "R5") (pin "2") (pinfunction "2_2") (pintype "passive"))
      (node (ref "U2") (pin "31") (pinfunction "PA10_31") (pintype "bidirectional"))
    )
    (net (code "52") (name "Net-(U2A-PD0-OSC_IN)") (class "Default")
      (node (ref "C13") (pin "2") (pinfunction "2_2") (pintype "passive"))
      (node (ref "U2") (pin "5") (pinfunction "PD0-OSC_IN_5") (pintype "bidirectional"))
      (node (ref "X1") (pin "3") (pinfunction "X2_3") (pintype "passive"))
    )
    (net (code "53") (name "Net-(U2A-PD1-OSC_OUT)") (class "Default")
      (node (ref "C14") (pin "2") (pinfunction "2_2") (pintype "passive"))
      (node (ref "U2") (pin "6") (pinfunction "PD1-OSC_OUT_6") (pintype "bidirectional"))
      (node (ref "X1") (pin "1") (pinfunction "X1_1") (pintype "passive"))
    )
    (net (code "54") (name "Net-(U3-C1+)") (class "Default")
      (node (ref "C8") (pin "2") (pinfunction "2_2") (pintype "passive"))
      (node (ref "U3") (pin "1") (pinfunction "C1+_1") (pintype "passive"))
    )
    (net (code "55") (name "Net-(U3-C1-)") (class "Default")
      (node (ref "C8") (pin "1") (pinfunction "1_1") (pintype "passive"))
      (node (ref "U3") (pin "3") (pinfunction "C1-_3") (pintype "passive"))
    )
    (net (code "56") (name "Net-(U3-C2+)") (class "Default")
      (node (ref "C9") (pin "2") (pinfunction "2_2") (pintype "passive"))
      (node (ref "U3") (pin "4") (pinfunction "C2+_4") (pintype "passive"))
    )
    (net (code "57") (name "Net-(U3-C2-)") (class "Default")
      (node (ref "C9") (pin "1") (pinfunction "1_1") (pintype "passive"))
      (node (ref "U3") (pin "5") (pinfunction "C2-_5") (pintype "passive"))
    )
    (net (code "58") (name "Net-(U3-V+)") (class "Default")
      (node (ref "C11") (pin "2") (pinfunction "2_2") (pintype "passive"))
      (node (ref "U3") (pin "2") (pinfunction "V+_2") (pintype "power_in"))
    )
    (net (code "59") (name "Net-(U3-V-)") (class "Default")
      (node (ref "C10") (pin "2") (pinfunction "2_2") (pintype "passive"))
      (node (ref "U3") (pin "6") (pinfunction "V-_6") (pintype "power_in"))
    )
    (net (code "60") (name "V_IN") (class "Default")
      (node (ref "D2") (pin "2") (pinfunction "A_2") (pintype "passive"))
      (node (ref "F2") (pin "1") (pinfunction "1_1") (pintype "passive"))
      (node (ref "J2") (pin "1") (pinfunction "1_1") (pintype "passive"))
      (node (ref "P2") (pin "14") (pinfunction "14_14") (pintype "passive"))
    )
    (net (code "61") (name "V_MCU") (class "Default")
      (node (ref "C6") (pin "2") (pinfunction "2_2") (pintype "passive"))
      (node (ref "D1") (pin "1") (pinfunction "K_1") (pintype "passive"))
      (node (ref "D2") (pin "1") (pinfunction "K_1") (pintype "passive"))
      (node (ref "D3") (pin "1") (pinfunction "K_1") (pintype "passive"))
      (node (ref "U1") (pin "3") (pinfunction "IN_3") (pintype "power_in"))
    )
    (net (code "62") (name "V_USB") (class "Default")
      (node (ref "D1") (pin "2") (pinfunction "A_2") (pintype "passive"))
      (node (ref "F1") (pin "1") (pinfunction "1_1") (pintype "passive"))
    )
    (net (code "63") (name "unconnected-(J1-ID-Pad4)") (class "Default")
      (node (ref "J1") (pin "4") (pinfunction "ID_4") (pintype "passive"))
    )
    (net (code "64") (name "unconnected-(J2-MH1-Pad11)") (class "Default")
      (node (ref "J2") (pin "11") (pinfunction "MH1_11") (pintype "passive"))
    )
    (net (code "65") (name "unconnected-(J2-MH2-Pad10)") (class "Default")
      (node (ref "J2") (pin "10") (pinfunction "MH2_10") (pintype "passive"))
    )
    (net (code "66") (name "unconnected-(J2-Pad6)") (class "Default")
      (node (ref "J2") (pin "6") (pinfunction "6_6") (pintype "passive"))
    )
    (net (code "67") (name "unconnected-(J4-Pad1)") (class "Default")
      (node (ref "J4") (pin "1") (pinfunction "1_1") (pintype "passive"))
    )
    (net (code "68") (name "unconnected-(J4-Pad4)") (class "Default")
      (node (ref "J4") (pin "4") (pinfunction "4_4") (pintype "passive"))
    )
    (net (code "69") (name "unconnected-(J4-Pad5)") (class "Default")
      (node (ref "J4") (pin "5") (pinfunction "5_5") (pintype "passive"))
    )
    (net (code "70") (name "unconnected-(U2A-PA0-WKUP-Pad10)") (class "Default")
      (node (ref "U2") (pin "10") (pinfunction "PA0-WKUP_10") (pintype "bidirectional"))
    )
    (net (code "71") (name "unconnected-(U2A-PB5-Pad41)") (class "Default")
      (node (ref "U2") (pin "41") (pinfunction "PB5_41") (pintype "bidirectional"))
    )
    (net (code "72") (name "unconnected-(U2A-PB13-Pad26)") (class "Default")
      (node (ref "U2") (pin "26") (pinfunction "PB13_26") (pintype "bidirectional"))
    )
    (net (code "73") (name "unconnected-(U2A-PB14-Pad27)") (class "Default")
      (node (ref "U2") (pin "27") (pinfunction "PB14_27") (pintype "bidirectional"))
    )
    (net (code "74") (name "unconnected-(U2A-PB15-Pad28)") (class "Default")
      (node (ref "U2") (pin "28") (pinfunction "PB15_28") (pintype "bidirectional"))
    )
    (net (code "75") (name "unconnected-(U4-SHDN-Pad5)") (class "Default")
      (node (ref "U4") (pin "5") (pinfunction "SHDN_5") (pintype "passive"))
    )
  )
)
